# DRVR_CIRCUIT.net
KiCad netlist of a schematic drawn in Altium Designer
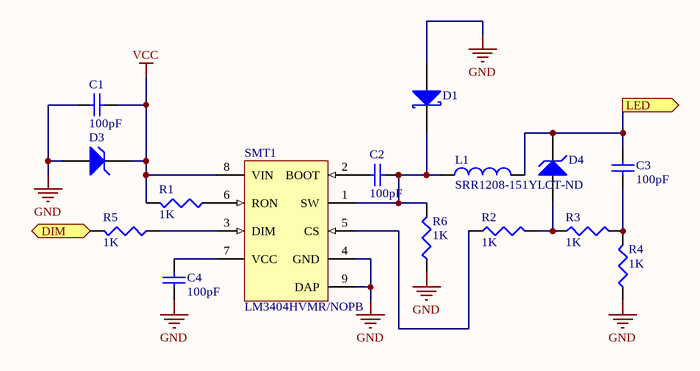
[diagram p0: DRVR_CIRCUIT.SchDoc]

(export (version "E")
  (design (tool "Eeschema 10.0.6"))
  (components
    (comp (ref "C1")
      (value "100pF")
      (footprint "C1206")
      (description "Capacitor (Semiconductor SIM Model)")
      (fields (field (name "Comment") "Cap Semi") (field (name "PUBLISHER") "Altium Limited"))
      (libsource (lib "Miscellaneous Devices") (part "Cap Semi"))
    )
    (comp (ref "C2")
      (value "100pF")
      (footprint "1608[0603]")
      (description "Capacitor (Semiconductor SIM Model)")
      (fields (field (name "Comment") "Cap Semi") (field (name "PUBLISHER") "Altium Limited"))
      (libsource (lib "Miscellaneous Devices") (part "Cap Semi"))
    )
    (comp (ref "C3")
      (value "100pF")
      (footprint "C1206")
      (description "Capacitor (Semiconductor SIM Model)")
      (fields (field (name "Comment") "Cap Semi") (field (name "PUBLISHER") "Altium Limited"))
      (libsource (lib "Miscellaneous Devices") (part "Cap Semi"))
    )
    (comp (ref "C4")
      (value "100pF")
      (footprint "1608[0603]")
      (description "Capacitor (Semiconductor SIM Model)")
      (fields (field (name "Comment") "Cap Semi") (field (name "PUBLISHER") "Altium Limited"))
      (libsource (lib "Miscellaneous Devices") (part "Cap Semi"))
    )
    (comp (ref "D1")
      (value "D Schottky")
      (footprint "SMB")
      (description "Schottky Diode")
      (fields (field (name "PUBLISHER") "Altium Limited"))
      (libsource (lib "Miscellaneous Devices") (part "D Schottky"))
    )
    (comp (ref "D3")
      (value "D Zener")
      (footprint "SMB")
      (description "Zener Diode")
      (fields (field (name "PUBLISHER") "Altium Limited"))
      (libsource (lib "Miscellaneous Devices") (part "D Zener"))
    )
    (comp (ref "D4")
      (value "D Zener")
      (footprint "SMB")
      (description "Zener Diode")
      (fields (field (name "PUBLISHER") "Altium Limited"))
      (libsource (lib "Miscellaneous Devices") (part "D Zener"))
    )
    (comp (ref "L1")
      (value "SRR1208-151YLCT-ND")
      (footprint "SRR1208-151YLCT-ND")
      (libsource (lib "Custom") (part "SRR1208-151YLCT-ND"))
    )
    (comp (ref "R1")
      (value "1K")
      (footprint "J1-0603")
      (description "Resistor")
      (fields (field (name "Comment") "Res3") (field (name "PUBLISHER") "Altium Limited"))
      (libsource (lib "Miscellaneous Devices") (part "Res3"))
    )
    (comp (ref "R2")
      (value "1K")
      (footprint "J1-0603")
      (description "Resistor")
      (fields (field (name "Comment") "Res3") (field (name "PUBLISHER") "Altium Limited"))
      (libsource (lib "Miscellaneous Devices") (part "Res3"))
    )
    (comp (ref "R3")
      (value "1K")
      (footprint "J1-0603")
      (description "Resistor")
      (fields (field (name "Comment") "Res3") (field (name "PUBLISHER") "Altium Limited"))
      (libsource (lib "Miscellaneous Devices") (part "Res3"))
    )
    (comp (ref "R4")
      (value "1K")
      (footprint "J1-0603")
      (description "Resistor")
      (fields (field (name "Comment") "Res3") (field (name "PUBLISHER") "Altium Limited"))
      (libsource (lib "Miscellaneous Devices") (part "Res3"))
    )
    (comp (ref "R5")
      (value "1K")
      (footprint "J1-0603")
      (description "Resistor")
      (fields (field (name "Comment") "Res3") (field (name "PUBLISHER") "Altium Limited"))
      (libsource (lib "Miscellaneous Devices") (part "Res3"))
    )
    (comp (ref "R6")
      (value "1K")
      (footprint "J1-0603")
      (description "Resistor")
      (fields (field (name "Comment") "Res3") (field (name "PUBLISHER") "Altium Limited"))
      (libsource (lib "Miscellaneous Devices") (part "Res3"))
    )
    (comp (ref "SMT1")
      (value "LM3404HVMR/NOPB")
      (footprint "MRA08B_M")
      (description "1.0A Constant Current Buck Regulator for High Power LED Drivers, 8-pin PSOP, Pb-Free")
      (fields
        (field (name "MANUFACTURER") "National Semiconductor")
        (field (name "PUBLISHER") "Altium Limited")
      )
      (libsource (lib "NSC MiscPower") (part "LM3404HVMR/NOPB"))
    )
  )
  (nets
    (net (code "1") (name "/DIM") (class "Default")
      (node (ref "R5") (pin "2") (pinfunction "2_2") (pintype "passive"))
    )
    (net (code "2") (name "/LED") (class "Default")
      (node (ref "C3") (pin "2") (pinfunction "2_2") (pintype "passive"))
      (node (ref "D4") (pin "2") (pinfunction "K_2") (pintype "passive"))
      (node (ref "L1") (pin "2") (pinfunction "2_2") (pintype "passive"))
    )
    (net (code "3") (name "GND") (class "Default")
      (node (ref "C1") (pin "1") (pinfunction "1_1") (pintype "passive"))
      (node (ref "C4") (pin "1") (pinfunction "1_1") (pintype "passive"))
      (node (ref "D1") (pin "1") (pinfunction "A_1") (pintype "passive"))
      (node (ref "D3") (pin "1") (pinfunction "A_1") (pintype "passive"))
      (node (ref "R4") (pin "1") (pinfunction "1_1") (pintype "passive"))
      (node (ref "R6") (pin "1") (pinfunction "1_1") (pintype "passive"))
      (node (ref "SMT1") (pin "4") (pinfunction "GND_4") (pintype "power_in"))
      (node (ref "SMT1") (pin "9") (pinfunction "DAP_9") (pintype "power_in"))
    )
    (net (code "4") (name "Net-(C3-Pad1)") (class "Default")
      (node (ref "C3") (pin "1") (pinfunction "1_1") (pintype "passive"))
      (node (ref "R3") (pin "2") (pinfunction "2_2") (pintype "passive"))
      (node (ref "R4") (pin "2") (pinfunction "2_2") (pintype "passive"))
    )
    (net (code "5") (name "Net-(D1-K)") (class "Default")
      (node (ref "C2") (pin "2") (pinfunction "2_2") (pintype "passive"))
      (node (ref "D1") (pin "2") (pinfunction "K_2") (pintype "passive"))
      (node (ref "L1") (pin "1") (pinfunction "1_1") (pintype "passive"))
      (node (ref "R6") (pin "2") (pinfunction "2_2") (pintype "passive"))
      (node (ref "SMT1") (pin "1") (pinfunction "SW_1") (pintype "power_in"))
    )
    (net (code "6") (name "Net-(D4-A)") (class "Default")
      (node (ref "D4") (pin "1") (pinfunction "A_1") (pintype "passive"))
      (node (ref "R2") (pin "2") (pinfunction "2_2") (pintype "passive"))
      (node (ref "R3") (pin "1") (pinfunction "1_1") (pintype "passive"))
    )
    (net (code "7") (name "Net-(SMT1-BOOT)") (class "Default")
      (node (ref "C2") (pin "1") (pinfunction "1_1") (pintype "passive"))
      (node (ref "SMT1") (pin "2") (pinfunction "BOOT_2") (pintype "input"))
    )
    (net (code "8") (name "Net-(SMT1-CS)") (class "Default")
      (node (ref "R2") (pin "1") (pinfunction "1_1") (pintype "passive"))
      (node (ref "SMT1") (pin "5") (pinfunction "CS_5") (pintype "input"))
    )
    (net (code "9") (name "Net-(SMT1-DIM)") (class "Default")
      (node (ref "R5") (pin "1") (pinfunction "1_1") (pintype "passive"))
      (node (ref "SMT1") (pin "3") (pinfunction "DIM_3") (pintype "input"))
    )
    (net (code "10") (name "Net-(SMT1-RON)") (class "Default")
      (node (ref "R1") (pin "1") (pinfunction "1_1") (pintype "passive"))
      (node (ref "SMT1") (pin "6") (pinfunction "RON_6") (pintype "input"))
    )
    (net (code "11") (name "Net-(SMT1-VCC)") (class "Default")
      (node (ref "C4") (pin "2") (pinfunction "2_2") (pintype "passive"))
      (node (ref "SMT1") (pin "7") (pinfunction "VCC_7") (pintype "power_in"))
    )
    (net (code "12") (name "VCC") (class "Default")
      (node (ref "C1") (pin "2") (pinfunction "2_2") (pintype "passive"))
      (node (ref "D3") (pin "2") (pinfunction "K_2") (pintype "passive"))
      (node (ref "R1") (pin "2") (pinfunction "2_2") (pintype "passive"))
      (node (ref "SMT1") (pin "8") (pinfunction "VIN_8") (pintype "power_in"))
    )
  )
)
